# dk_binh_nuoc_nong.net
KiCad netlist of a schematic drawn in Altium Designer
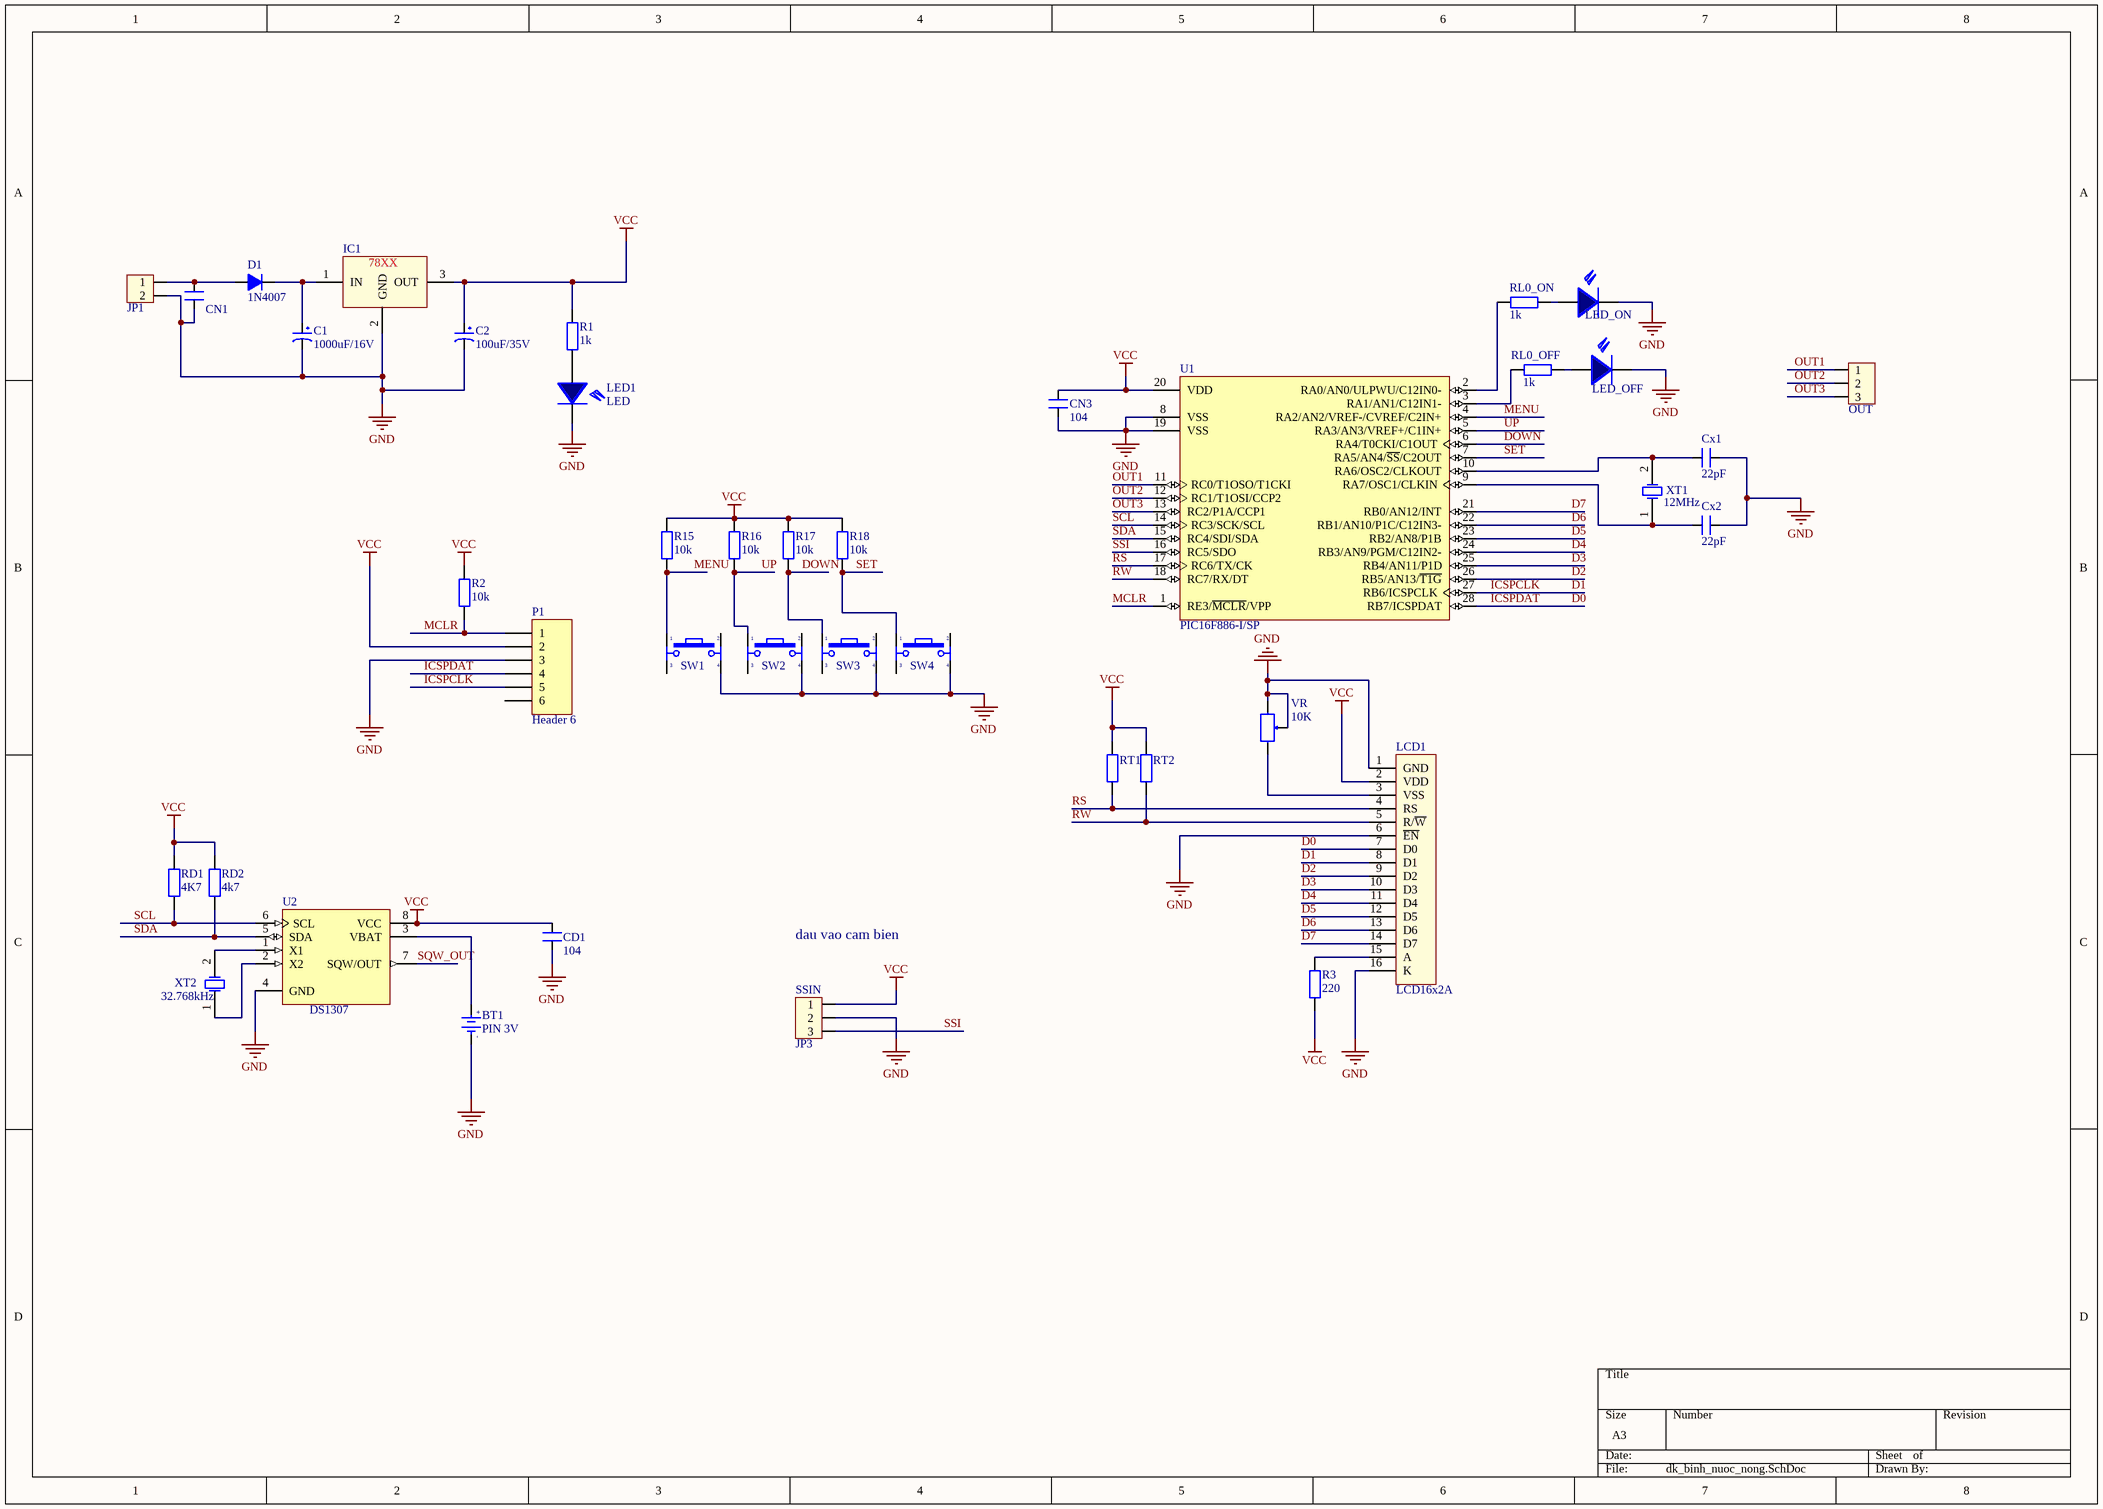
[diagram p0: dk_binh_nuoc_nong.SchDoc]

(export (version "E")
  (design (tool "Eeschema 10.0.6"))
  (components
    (comp (ref "BT1")
      (value "PIN 3V")
      (footprint "PIN3V")
      (description "Battery 3VDC")
      (libsource (lib "Duy_Schematic") (part "PIN 3V"))
    )
    (comp (ref "C1")
      (value "1000uF/16V")
      (footprint "CP1.5/3.4")
      (description "Cap 1000uF/16V - 220uF/50V")
      (libsource (lib "Duy_Schematic") (part "CP4"))
    )
    (comp (ref "C2")
      (value "100uF/35V")
      (footprint "CP1.5/3.4")
      (description "Cap 100uF/35V - 470uF/16V")
      (libsource (lib "Duy_Schematic") (part "CP3"))
    )
    (comp (ref "CD1")
      (value "104")
      (footprint "CN2")
      (description "Cap np Cremic Value  104pF => 105pF")
      (libsource (lib "Duy_Schematic") (part "CN2"))
    )
    (comp (ref "CN1")
      (value "104")
      (footprint "CN1")
      (description "Cap np Cremic Value  104pF => 105pF")
      (libsource (lib "Duy_Schematic") (part "CN2"))
    )
    (comp (ref "CN3")
      (value "104")
      (footprint "CN1")
      (description "Cap np Cremic Value  104pF => 105pF")
      (libsource (lib "Duy_Schematic") (part "CN2"))
    )
    (comp (ref "Cx1")
      (value "22pF")
      (footprint "CN1")
      (description "Cap np Cremic value 1pF => 100pF")
      (libsource (lib "Duy_Schematic") (part "CN0"))
    )
    (comp (ref "Cx2")
      (value "22pF")
      (footprint "CN1")
      (description "Cap np Cremic value 1pF => 100pF")
      (libsource (lib "Duy_Schematic") (part "CN0"))
    )
    (comp (ref "D1")
      (value "1N4007")
      (footprint "D1A")
      (description "Diode 1A")
      (libsource (lib "Duy_Schematic") (part "D1A"))
    )
    (comp (ref "IC1") (value "78xx") (footprint "QTO-220") (libsource (lib "Duy_Schematic") (part "78xx")))
    (comp (ref "JP1")
      (value "JP2")
      (footprint "CON2")
      (description "Connector 2")
      (libsource (lib "Duy_Schematic") (part "Con2"))
    )
    (comp (ref "LCD1")
      (value "LCD16x2A")
      (footprint "LCD16X2")
      (description "LCD dipslay 16 char, 2 line")
      (libsource (lib "Duy_Schematic") (part "LCD16x2"))
    )
    (comp (ref "LED1")
      (value "LED")
      (footprint "LED-3")
      (description "Led  Vuong")
      (libsource (lib "Duy_Schematic") (part "LED"))
    )
    (comp (ref "LED_OFF")
      (value "LED")
      (footprint "LED-3")
      (description "Led  Vuong")
      (libsource (lib "Duy_Schematic") (part "LED"))
    )
    (comp (ref "LED_ON")
      (value "LED")
      (footprint "LED-3")
      (description "Led  Vuong")
      (libsource (lib "Duy_Schematic") (part "LED"))
    )
    (comp (ref "OUT")
      (value "JP3")
      (footprint "CON3")
      (description "Connector 3")
      (libsource (lib "Duy_Schematic") (part "Con3"))
    )
    (comp (ref "P1")
      (value "Header 6")
      (footprint "HED6")
      (description "Header, 6-Pin")
      (fields (field (name "PUBLISHER") "Altium Limited"))
      (libsource (lib "Miscellaneous Connectors") (part "Header 6"))
    )
    (comp (ref "R1")
      (value "1k")
      (footprint "R1/4W")
      (description "Resistor 1/4W")
      (libsource (lib "Duy_Schematic") (part "R1/4W"))
    )
    (comp (ref "R2")
      (value "10k")
      (footprint "R1/4W")
      (description "Resistor 1/4W")
      (libsource (lib "Duy_Schematic") (part "R1/4W"))
    )
    (comp (ref "R3")
      (value "220")
      (footprint "R1/4W")
      (description "Resistor 1/4W")
      (libsource (lib "Duy_Schematic") (part "R1/4W"))
    )
    (comp (ref "R15")
      (value "10k")
      (footprint "R1/4W")
      (description "Resistor 1/4W")
      (libsource (lib "Duy_Schematic") (part "R1/4W"))
    )
    (comp (ref "R16")
      (value "10k")
      (footprint "R1/4W")
      (description "Resistor 1/4W")
      (libsource (lib "Duy_Schematic") (part "R1/4W"))
    )
    (comp (ref "R17")
      (value "10k")
      (footprint "R1/4W")
      (description "Resistor 1/4W")
      (libsource (lib "Duy_Schematic") (part "R1/4W"))
    )
    (comp (ref "R18")
      (value "10k")
      (footprint "R1/4W")
      (description "Resistor 1/4W")
      (libsource (lib "Duy_Schematic") (part "R1/4W"))
    )
    (comp (ref "RD1")
      (value "4K7")
      (footprint "R1/4W")
      (description "Resistor 1/4W")
      (libsource (lib "Duy_Schematic") (part "R1/4W"))
    )
    (comp (ref "RD2")
      (value "4k7")
      (footprint "R1/4W")
      (description "Resistor 1/4W")
      (libsource (lib "Duy_Schematic") (part "R1/4W"))
    )
    (comp (ref "RL0_OFF")
      (value "1k")
      (footprint "R1/4W")
      (description "Resistor 1/4W")
      (libsource (lib "Duy_Schematic") (part "R1/4W"))
    )
    (comp (ref "RL0_ON")
      (value "1k")
      (footprint "R1/4W")
      (description "Resistor 1/4W")
      (libsource (lib "Duy_Schematic") (part "R1/4W"))
    )
    (comp (ref "RT1")
      (value "10K")
      (footprint "R1/4W")
      (description "Resistor 1/4W")
      (libsource (lib "Duy_Schematic") (part "R1/4W"))
    )
    (comp (ref "RT2")
      (value "10K")
      (footprint "R1/4W")
      (description "Resistor 1/4W")
      (libsource (lib "Duy_Schematic") (part "R1/4W"))
    )
    (comp (ref "SSIN")
      (value "JP3")
      (footprint "CON3")
      (description "Connector 3")
      (libsource (lib "") (part "Con3_1"))
    )
    (comp (ref "SW1")
      (value "SW")
      (footprint "SW4")
      (description "Switch button 4 pin")
      (libsource (lib "Duy_Schematic") (part "SW4"))
    )
    (comp (ref "SW2")
      (value "SW")
      (footprint "SW4")
      (description "Switch button 4 pin")
      (libsource (lib "Duy_Schematic") (part "SW4"))
    )
    (comp (ref "SW3")
      (value "SW")
      (footprint "SW4")
      (description "Switch button 4 pin")
      (libsource (lib "Duy_Schematic") (part "SW4"))
    )
    (comp (ref "SW4")
      (value "SW")
      (footprint "SW4")
      (description "Switch button 4 pin")
      (libsource (lib "Duy_Schematic") (part "SW4"))
    )
    (comp (ref "U1")
      (value "PIC16F886-I/SP")
      (footprint "DIP28/W0.3")
      (fields (field (name "PUBLISHER") "Altium Limited"))
      (libsource (lib "Microchip Microcontroller 8-Bit PIC16") (part "PIC16F886-I/SP"))
    )
    (comp (ref "U2")
      (value "DS1307")
      (footprint "DIP8/W0.3")
      (description "64 X 8 Serial Real-Time Clock")
      (fields (field (name "PUBLISHER") "Altium Limited"))
      (libsource (lib "Dallas Peripheral Real Time Clock") (part "DS1307"))
    )
    (comp (ref "VR")
      (value "10K")
      (footprint "VR")
      (description "Var Resistor")
      (libsource (lib "Duy_Schematic") (part "VR"))
    )
    (comp (ref "XT1")
      (value "12MHz")
      (footprint "XT2")
      (description "Crystal Oscillator")
      (fields (field (name "PUBLISHER") "Altium Limited"))
      (libsource (lib "Miscellaneous Devices") (part "XTAL"))
    )
    (comp (ref "XT2")
      (value "32.768kHz")
      (footprint "XT32k")
      (description "Crystal Oscillator")
      (fields (field (name "PUBLISHER") "Altium Limited"))
      (libsource (lib "Miscellaneous Devices") (part "XTAL"))
    )
  )
  (nets
    (net (code "1") (name "/D0") (class "Default")
      (node (ref "LCD1") (pin "7") (pinfunction "D0_7") (pintype "passive"))
      (node (ref "P1") (pin "4") (pinfunction "4_4") (pintype "passive"))
      (node (ref "U1") (pin "28") (pinfunction "RB7/ICSPDAT_28") (pintype "bidirectional"))
    )
    (net (code "2") (name "/D1") (class "Default")
      (node (ref "LCD1") (pin "8") (pinfunction "D1_8") (pintype "passive"))
      (node (ref "P1") (pin "5") (pinfunction "5_5") (pintype "passive"))
      (node (ref "U1") (pin "27") (pinfunction "RB6/ICSPCLK_27") (pintype "bidirectional"))
    )
    (net (code "3") (name "/D2") (class "Default")
      (node (ref "LCD1") (pin "9") (pinfunction "D2_9") (pintype "passive"))
      (node (ref "U1") (pin "26") (pinfunction "RB5/AN13/~{T1G}_26") (pintype "bidirectional"))
    )
    (net (code "4") (name "/D3") (class "Default")
      (node (ref "LCD1") (pin "10") (pinfunction "D3_10") (pintype "passive"))
      (node (ref "U1") (pin "25") (pinfunction "RB4/AN11/P1D_25") (pintype "bidirectional"))
    )
    (net (code "5") (name "/D4") (class "Default")
      (node (ref "LCD1") (pin "11") (pinfunction "D4_11") (pintype "passive"))
      (node (ref "U1") (pin "24") (pinfunction "RB3/AN9/PGM/C12IN2-_24") (pintype "bidirectional"))
    )
    (net (code "6") (name "/D5") (class "Default")
      (node (ref "LCD1") (pin "12") (pinfunction "D5_12") (pintype "passive"))
      (node (ref "U1") (pin "23") (pinfunction "RB2/AN8/P1B_23") (pintype "bidirectional"))
    )
    (net (code "7") (name "/D6") (class "Default")
      (node (ref "LCD1") (pin "13") (pinfunction "D6_13") (pintype "passive"))
      (node (ref "U1") (pin "22") (pinfunction "RB1/AN10/P1C/C12IN3-_22") (pintype "bidirectional"))
    )
    (net (code "8") (name "/D7") (class "Default")
      (node (ref "LCD1") (pin "14") (pinfunction "D7_14") (pintype "passive"))
      (node (ref "U1") (pin "21") (pinfunction "RB0/AN12/INT_21") (pintype "bidirectional"))
    )
    (net (code "9") (name "/DOWN") (class "Default")
      (node (ref "R17") (pin "1") (pinfunction "1_1") (pintype "passive"))
      (node (ref "SW3") (pin "1") (pinfunction "1_1") (pintype "passive"))
      (node (ref "U1") (pin "6") (pinfunction "RA4/T0CKI/C1OUT_6") (pintype "bidirectional"))
    )
    (net (code "10") (name "/MCLR") (class "Default")
      (node (ref "P1") (pin "1") (pinfunction "1_1") (pintype "passive"))
      (node (ref "R2") (pin "1") (pinfunction "1_1") (pintype "passive"))
      (node (ref "U1") (pin "1") (pinfunction "RE3/~{MCLR}/VPP_1") (pintype "bidirectional"))
    )
    (net (code "11") (name "/MENU") (class "Default")
      (node (ref "R15") (pin "1") (pinfunction "1_1") (pintype "passive"))
      (node (ref "SW1") (pin "1") (pinfunction "1_1") (pintype "passive"))
      (node (ref "U1") (pin "4") (pinfunction "RA2/AN2/VREF-/CVREF/C2IN+_4") (pintype "bidirectional"))
    )
    (net (code "12") (name "/OUT1") (class "Default")
      (node (ref "OUT") (pin "1") (pinfunction "1_1") (pintype "passive"))
      (node (ref "U1") (pin "11") (pinfunction "RC0/T1OSO/T1CKI_11") (pintype "bidirectional"))
    )
    (net (code "13") (name "/OUT2") (class "Default")
      (node (ref "OUT") (pin "2") (pinfunction "2_2") (pintype "passive"))
      (node (ref "U1") (pin "12") (pinfunction "RC1/T1OSI/CCP2_12") (pintype "bidirectional"))
    )
    (net (code "14") (name "/OUT3") (class "Default")
      (node (ref "OUT") (pin "3") (pinfunction "3_3") (pintype "passive"))
      (node (ref "U1") (pin "13") (pinfunction "RC2/P1A/CCP1_13") (pintype "bidirectional"))
    )
    (net (code "15") (name "/RS") (class "Default")
      (node (ref "LCD1") (pin "4") (pinfunction "RS_4") (pintype "passive"))
      (node (ref "RT1") (pin "1") (pinfunction "1_1") (pintype "passive"))
      (node (ref "U1") (pin "17") (pinfunction "RC6/TX/CK_17") (pintype "bidirectional"))
    )
    (net (code "16") (name "/RW") (class "Default")
      (node (ref "LCD1") (pin "5") (pinfunction "R/~{W}_5") (pintype "passive"))
      (node (ref "RT2") (pin "1") (pinfunction "1_1") (pintype "passive"))
      (node (ref "U1") (pin "18") (pinfunction "RC7/RX/DT_18") (pintype "bidirectional"))
    )
    (net (code "17") (name "/SCL") (class "Default")
      (node (ref "RD1") (pin "1") (pinfunction "1_1") (pintype "passive"))
      (node (ref "U1") (pin "14") (pinfunction "RC3/SCK/SCL_14") (pintype "bidirectional"))
      (node (ref "U2") (pin "6") (pinfunction "SCL_6") (pintype "input"))
    )
    (net (code "18") (name "/SDA") (class "Default")
      (node (ref "RD2") (pin "1") (pinfunction "1_1") (pintype "passive"))
      (node (ref "U1") (pin "15") (pinfunction "RC4/SDI/SDA_15") (pintype "bidirectional"))
      (node (ref "U2") (pin "5") (pinfunction "SDA_5") (pintype "bidirectional"))
    )
    (net (code "19") (name "/SET") (class "Default")
      (node (ref "R18") (pin "1") (pinfunction "1_1") (pintype "passive"))
      (node (ref "SW4") (pin "1") (pinfunction "1_1") (pintype "passive"))
      (node (ref "U1") (pin "7") (pinfunction "RA5/AN4/~{SS}/C2OUT_7") (pintype "bidirectional"))
    )
    (net (code "20") (name "/SQW_OUT") (class "Default")
      (node (ref "U2") (pin "7") (pinfunction "SQW/OUT_7") (pintype "output"))
    )
    (net (code "21") (name "/SSI") (class "Default")
      (node (ref "SSIN") (pin "3") (pinfunction "3_3") (pintype "passive"))
      (node (ref "U1") (pin "16") (pinfunction "RC5/SDO_16") (pintype "bidirectional"))
    )
    (net (code "22") (name "/UP") (class "Default")
      (node (ref "R16") (pin "1") (pinfunction "1_1") (pintype "passive"))
      (node (ref "SW2") (pin "1") (pinfunction "1_1") (pintype "passive"))
      (node (ref "U1") (pin "5") (pinfunction "RA3/AN3/VREF+/C1IN+_5") (pintype "bidirectional"))
    )
    (net (code "23") (name "GND") (class "Default")
      (node (ref "BT1") (pin "2") (pinfunction "GND_2") (pintype "passive"))
      (node (ref "C1") (pin "2") (pinfunction "2_2") (pintype "passive"))
      (node (ref "C2") (pin "2") (pinfunction "2_2") (pintype "passive"))
      (node (ref "CD1") (pin "1") (pinfunction "1_1") (pintype "passive"))
      (node (ref "CN1") (pin "1") (pinfunction "1_1") (pintype "passive"))
      (node (ref "CN3") (pin "1") (pinfunction "1_1") (pintype "passive"))
      (node (ref "Cx1") (pin "2") (pinfunction "2_2") (pintype "passive"))
      (node (ref "Cx2") (pin "2") (pinfunction "2_2") (pintype "passive"))
      (node (ref "IC1") (pin "2") (pinfunction "GND_2") (pintype "passive"))
      (node (ref "JP1") (pin "2") (pinfunction "2_2") (pintype "passive"))
      (node (ref "LCD1") (pin "1") (pinfunction "GND_1") (pintype "passive"))
      (node (ref "LCD1") (pin "16") (pinfunction "K_16") (pintype "passive"))
      (node (ref "LCD1") (pin "6") (pinfunction "~{EN}_6") (pintype "passive"))
      (node (ref "LED1") (pin "2") (pinfunction "2_2") (pintype "passive"))
      (node (ref "LED_OFF") (pin "2") (pinfunction "2_2") (pintype "passive"))
      (node (ref "LED_ON") (pin "2") (pinfunction "2_2") (pintype "passive"))
      (node (ref "P1") (pin "3") (pinfunction "3_3") (pintype "passive"))
      (node (ref "SSIN") (pin "2") (pinfunction "2_2") (pintype "passive"))
      (node (ref "SW1") (pin "4") (pinfunction "4_4") (pintype "passive"))
      (node (ref "SW2") (pin "4") (pinfunction "4_4") (pintype "passive"))
      (node (ref "SW3") (pin "4") (pinfunction "4_4") (pintype "passive"))
      (node (ref "SW4") (pin "4") (pinfunction "4_4") (pintype "passive"))
      (node (ref "U1") (pin "19") (pinfunction "VSS_19") (pintype "power_in"))
      (node (ref "U1") (pin "8") (pinfunction "VSS_8") (pintype "power_in"))
      (node (ref "U2") (pin "4") (pinfunction "GND_4") (pintype "power_in"))
      (node (ref "VR") (pin "1") (pinfunction "1_1") (pintype "passive"))
      (node (ref "VR") (pin "2") (pinfunction "2_2") (pintype "passive"))
    )
    (net (code "24") (name "Net-(BT1-+3V)") (class "Default")
      (node (ref "BT1") (pin "1") (pinfunction "+3V_1") (pintype "passive"))
      (node (ref "U2") (pin "3") (pinfunction "VBAT_3") (pintype "power_in"))
    )
    (net (code "25") (name "Net-(D1-A)") (class "Default")
      (node (ref "CN1") (pin "2") (pinfunction "2_2") (pintype "passive"))
      (node (ref "D1") (pin "1") (pinfunction "A_1") (pintype "passive"))
      (node (ref "JP1") (pin "1") (pinfunction "1_1") (pintype "passive"))
    )
    (net (code "26") (name "Net-(D1-K)") (class "Default")
      (node (ref "C1") (pin "1") (pinfunction "1_1") (pintype "passive"))
      (node (ref "D1") (pin "2") (pinfunction "K_2") (pintype "passive"))
      (node (ref "IC1") (pin "1") (pinfunction "IN_1") (pintype "passive"))
    )
    (net (code "27") (name "Net-(LCD1-A)") (class "Default")
      (node (ref "LCD1") (pin "15") (pinfunction "A_15") (pintype "passive"))
      (node (ref "R3") (pin "2") (pinfunction "2_2") (pintype "passive"))
    )
    (net (code "28") (name "Net-(LCD1-VSS)") (class "Default")
      (node (ref "LCD1") (pin "3") (pinfunction "VSS_3") (pintype "passive"))
      (node (ref "VR") (pin "3") (pinfunction "3_3") (pintype "passive"))
    )
    (net (code "29") (name "Net-(LED1-Pad1)") (class "Default")
      (node (ref "LED1") (pin "1") (pinfunction "1_1") (pintype "passive"))
      (node (ref "R1") (pin "1") (pinfunction "1_1") (pintype "passive"))
    )
    (net (code "30") (name "Net-(LED_OFF-Pad1)") (class "Default")
      (node (ref "LED_OFF") (pin "1") (pinfunction "1_1") (pintype "passive"))
      (node (ref "RL0_OFF") (pin "1") (pinfunction "1_1") (pintype "passive"))
    )
    (net (code "31") (name "Net-(LED_ON-Pad1)") (class "Default")
      (node (ref "LED_ON") (pin "1") (pinfunction "1_1") (pintype "passive"))
      (node (ref "RL0_ON") (pin "1") (pinfunction "1_1") (pintype "passive"))
    )
    (net (code "32") (name "Net-(U1-RA0{slash}AN0{slash}ULPWU{slash}C12IN0-)") (class "Default")
      (node (ref "RL0_ON") (pin "2") (pinfunction "2_2") (pintype "passive"))
      (node (ref "U1") (pin "2") (pinfunction "RA0/AN0/ULPWU/C12IN0-_2") (pintype "bidirectional"))
    )
    (net (code "33") (name "Net-(U1-RA1{slash}AN1{slash}C12IN1-)") (class "Default")
      (node (ref "RL0_OFF") (pin "2") (pinfunction "2_2") (pintype "passive"))
      (node (ref "U1") (pin "3") (pinfunction "RA1/AN1/C12IN1-_3") (pintype "bidirectional"))
    )
    (net (code "34") (name "Net-(U1-RA6{slash}OSC2{slash}CLKOUT)") (class "Default")
      (node (ref "Cx1") (pin "1") (pinfunction "1_1") (pintype "passive"))
      (node (ref "U1") (pin "10") (pinfunction "RA6/OSC2/CLKOUT_10") (pintype "bidirectional"))
      (node (ref "XT1") (pin "2") (pinfunction "OSC2_2") (pintype "passive"))
    )
    (net (code "35") (name "Net-(U1-RA7{slash}OSC1{slash}CLKIN)") (class "Default")
      (node (ref "Cx2") (pin "1") (pinfunction "1_1") (pintype "passive"))
      (node (ref "U1") (pin "9") (pinfunction "RA7/OSC1/CLKIN_9") (pintype "bidirectional"))
      (node (ref "XT1") (pin "1") (pinfunction "OSC1_1") (pintype "passive"))
    )
    (net (code "36") (name "Net-(U2-X1)") (class "Default")
      (node (ref "U2") (pin "1") (pinfunction "X1_1") (pintype "input"))
      (node (ref "XT2") (pin "2") (pinfunction "OSC2_2") (pintype "passive"))
    )
    (net (code "37") (name "Net-(U2-X2)") (class "Default")
      (node (ref "U2") (pin "2") (pinfunction "X2_2") (pintype "input"))
      (node (ref "XT2") (pin "1") (pinfunction "OSC1_1") (pintype "passive"))
    )
    (net (code "38") (name "VCC") (class "Default")
      (node (ref "C2") (pin "1") (pinfunction "1_1") (pintype "passive"))
      (node (ref "CD1") (pin "2") (pinfunction "2_2") (pintype "passive"))
      (node (ref "CN3") (pin "2") (pinfunction "2_2") (pintype "passive"))
      (node (ref "IC1") (pin "3") (pinfunction "OUT_3") (pintype "passive"))
      (node (ref "LCD1") (pin "2") (pinfunction "VDD_2") (pintype "passive"))
      (node (ref "P1") (pin "2") (pinfunction "2_2") (pintype "passive"))
      (node (ref "R1") (pin "2") (pinfunction "2_2") (pintype "passive"))
      (node (ref "R15") (pin "2") (pinfunction "2_2") (pintype "passive"))
      (node (ref "R16") (pin "2") (pinfunction "2_2") (pintype "passive"))
      (node (ref "R17") (pin "2") (pinfunction "2_2") (pintype "passive"))
      (node (ref "R18") (pin "2") (pinfunction "2_2") (pintype "passive"))
      (node (ref "R2") (pin "2") (pinfunction "2_2") (pintype "passive"))
      (node (ref "R3") (pin "1") (pinfunction "1_1") (pintype "passive"))
      (node (ref "RD1") (pin "2") (pinfunction "2_2") (pintype "passive"))
      (node (ref "RD2") (pin "2") (pinfunction "2_2") (pintype "passive"))
      (node (ref "RT1") (pin "2") (pinfunction "2_2") (pintype "passive"))
      (node (ref "RT2") (pin "2") (pinfunction "2_2") (pintype "passive"))
      (node (ref "SSIN") (pin "1") (pinfunction "1_1") (pintype "passive"))
      (node (ref "U1") (pin "20") (pinfunction "VDD_20") (pintype "power_in"))
      (node (ref "U2") (pin "8") (pinfunction "VCC_8") (pintype "power_in"))
    )
    (net (code "39") (name "unconnected-(P1-Pad6)") (class "Default")
      (node (ref "P1") (pin "6") (pinfunction "6_6") (pintype "passive"))
    )
    (net (code "40") (name "unconnected-(SW1-Pad2)") (class "Default")
      (node (ref "SW1") (pin "2") (pinfunction "2_2") (pintype "passive"))
    )
    (net (code "41") (name "unconnected-(SW1-Pad3)") (class "Default")
      (node (ref "SW1") (pin "3") (pinfunction "3_3") (pintype "passive"))
    )
    (net (code "42") (name "unconnected-(SW2-Pad2)") (class "Default")
      (node (ref "SW2") (pin "2") (pinfunction "2_2") (pintype "passive"))
    )
    (net (code "43") (name "unconnected-(SW2-Pad3)") (class "Default")
      (node (ref "SW2") (pin "3") (pinfunction "3_3") (pintype "passive"))
    )
    (net (code "44") (name "unconnected-(SW3-Pad2)") (class "Default")
      (node (ref "SW3") (pin "2") (pinfunction "2_2") (pintype "passive"))
    )
    (net (code "45") (name "unconnected-(SW3-Pad3)") (class "Default")
      (node (ref "SW3") (pin "3") (pinfunction "3_3") (pintype "passive"))
    )
    (net (code "46") (name "unconnected-(SW4-Pad2)") (class "Default")
      (node (ref "SW4") (pin "2") (pinfunction "2_2") (pintype "passive"))
    )
    (net (code "47") (name "unconnected-(SW4-Pad3)") (class "Default")
      (node (ref "SW4") (pin "3") (pinfunction "3_3") (pintype "passive"))
    )
  )
)
